# skema_gambar_teknik.net
KiCad netlist of a schematic drawn in EAGLE
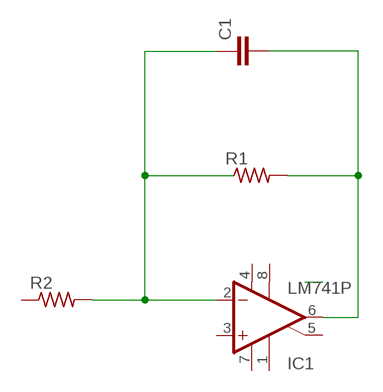
[diagram p0: schematic, sheet 1]

(export (version "E")
  (design (tool "Eeschema 10.0.6"))
  (components
    (comp (ref "C1")
      (value "C-EUC0603")
      (footprint "eagle-import:C0603")
      (libsource (lib "eagle-import") (part "C-EUC0603"))
    )
    (comp (ref "IC1")
      (value "LM741P")
      (footprint "eagle-import:DIL08")
      (libsource (lib "eagle-import") (part "741PLM"))
    )
    (comp (ref "R1")
      (value "R-US_R0603")
      (footprint "eagle-import:R0603")
      (libsource (lib "eagle-import") (part "R-US_R0603"))
    )
    (comp (ref "R2")
      (value "R-US_R0603")
      (footprint "eagle-import:R0603")
      (libsource (lib "eagle-import") (part "R-US_R0603"))
    )
  )
  (nets
    (net (code "1") (name "/V+") (class "Default")
      (node (ref "IC1") (pin "7") (pinfunction "V+_7") (pintype "power_in"))
    )
    (net (code "2") (name "/V-") (class "Default")
      (node (ref "IC1") (pin "4") (pinfunction "V-_4") (pintype "power_in"))
    )
    (net (code "3") (name "Net-(IC1--IN)") (class "Default")
      (node (ref "C1") (pin "1") (pinfunction "1_1") (pintype "passive"))
      (node (ref "IC1") (pin "2") (pinfunction "-IN_2") (pintype "input"))
      (node (ref "R2") (pin "2") (pinfunction "2_2") (pintype "passive"))
    )
    (net (code "4") (name "Net-(IC1-OUT)") (class "Default")
      (node (ref "C1") (pin "2") (pinfunction "2_2") (pintype "passive"))
      (node (ref "IC1") (pin "6") (pinfunction "OUT_6") (pintype "output"))
      (node (ref "R1") (pin "2") (pinfunction "2_2") (pintype "passive"))
    )
    (net (code "5") (name "unconnected-(IC1-+IN-Pad3)") (class "Default")
      (node (ref "IC1") (pin "3") (pinfunction "+IN_3") (pintype "input"))
    )
    (net (code "6") (name "unconnected-(IC1-ON1-Pad1)") (class "Default")
      (node (ref "IC1") (pin "1") (pinfunction "ON1_1") (pintype "passive"))
    )
    (net (code "7") (name "unconnected-(IC1-ON2-Pad5)") (class "Default")
      (node (ref "IC1") (pin "5") (pinfunction "ON2_5") (pintype "passive"))
    )
    (net (code "8") (name "unconnected-(IC1-OPT-Pad8)") (class "Default")
      (node (ref "IC1") (pin "8") (pinfunction "OPT_8") (pintype "passive"))
    )
    (net (code "9") (name "unconnected-(R1-Pad1)") (class "Default")
      (node (ref "R1") (pin "1") (pinfunction "1_1") (pintype "passive"))
    )
    (net (code "10") (name "unconnected-(R2-Pad1)") (class "Default")
      (node (ref "R2") (pin "1") (pinfunction "1_1") (pintype "passive"))
    )
  )
)
